# Dodekatron.net
KiCad netlist of a schematic drawn in EAGLE
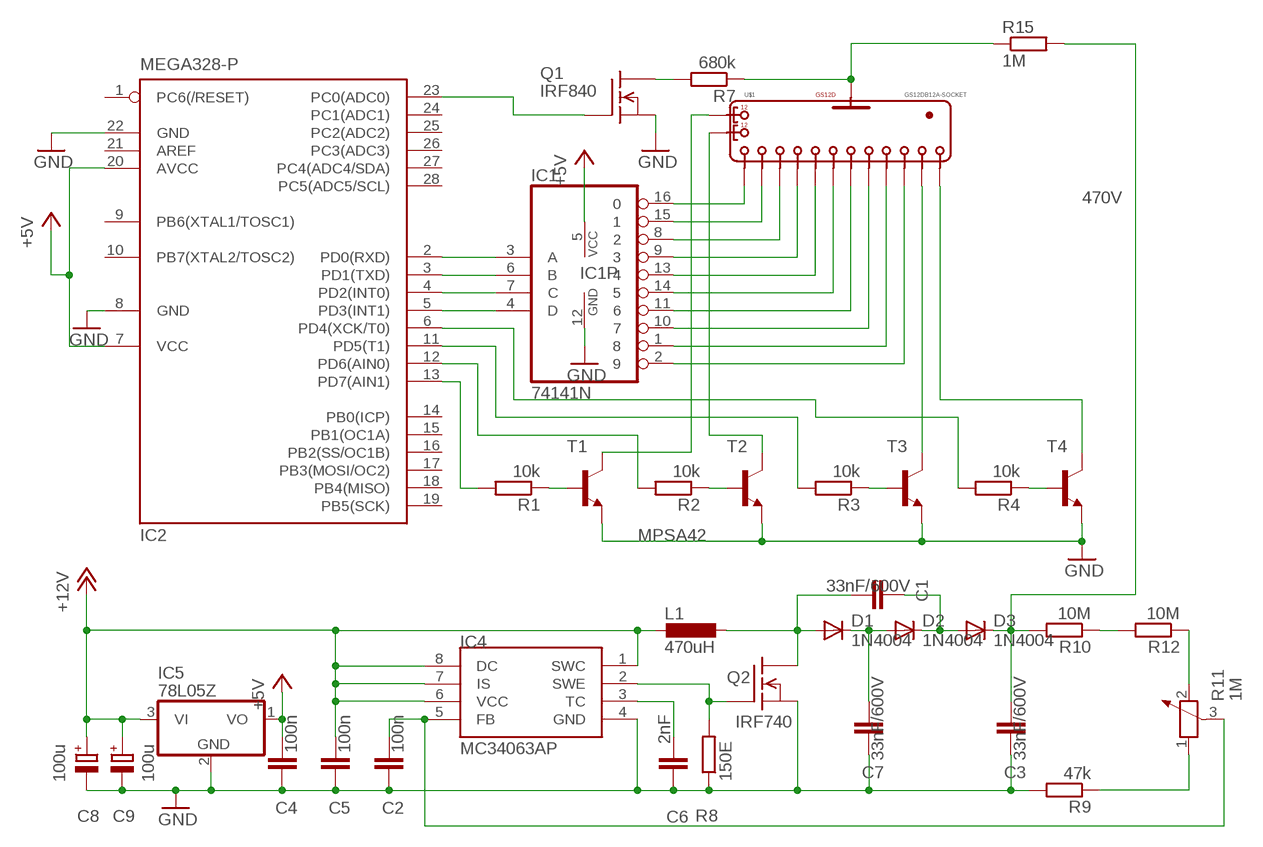
[diagram p0: schematic, sheet 1]

(export (version "E")
  (design (tool "Eeschema 10.0.6"))
  (components
    (comp (ref "C1")
      (value "33nF/600V")
      (footprint "eagle-import:C025-025X050")
      (libsource (lib "eagle-import") (part "C-EU025-025X050"))
    )
    (comp (ref "C2")
      (value "100n")
      (footprint "eagle-import:C025-025X050")
      (libsource (lib "eagle-import") (part "C-EU025-025X050"))
    )
    (comp (ref "C3")
      (value "33nF/600V")
      (footprint "eagle-import:C025-025X050")
      (libsource (lib "eagle-import") (part "C-EU025-025X050"))
    )
    (comp (ref "C4")
      (value "100n")
      (footprint "eagle-import:C025-025X050")
      (libsource (lib "eagle-import") (part "C-EU025-025X050"))
    )
    (comp (ref "C5")
      (value "100n")
      (footprint "eagle-import:C025-025X050")
      (libsource (lib "eagle-import") (part "C-EU025-025X050"))
    )
    (comp (ref "C6")
      (value "2nF")
      (footprint "eagle-import:C025-025X050")
      (libsource (lib "eagle-import") (part "C-EU025-025X050"))
    )
    (comp (ref "C7")
      (value "33nF/600V")
      (footprint "eagle-import:C025-025X050")
      (libsource (lib "eagle-import") (part "C-EU025-025X050"))
    )
    (comp (ref "C8")
      (value "100u")
      (footprint "eagle-import:TAP5-80")
      (libsource (lib "eagle-import") (part "CPOL-EUTAP5-80"))
    )
    (comp (ref "C9")
      (value "100u")
      (footprint "eagle-import:TAP5-80")
      (libsource (lib "eagle-import") (part "CPOL-EUTAP5-80"))
    )
    (comp (ref "D1")
      (value "1N4004")
      (footprint "eagle-import:DO41-10")
      (libsource (lib "eagle-import") (part "1N4004"))
    )
    (comp (ref "D2")
      (value "1N4004")
      (footprint "eagle-import:DO41-10")
      (libsource (lib "eagle-import") (part "1N4004"))
    )
    (comp (ref "D3")
      (value "1N4004")
      (footprint "eagle-import:DO41-10")
      (libsource (lib "eagle-import") (part "1N4004"))
    )
    (comp (ref "IC1")
      (value "74141N")
      (footprint "eagle-import:DIL16")
      (libsource (lib "eagle-import") (part "74141N"))
    )
    (comp (ref "IC2")
      (value "MEGA328-P")
      (footprint "eagle-import:DIL28-3")
      (libsource (lib "eagle-import") (part "MEGA8-P"))
    )
    (comp (ref "IC4")
      (value "MC34063AP")
      (footprint "eagle-import:DIL08")
      (libsource (lib "eagle-import") (part "MC34063AP"))
    )
    (comp (ref "IC5")
      (value "78L05Z")
      (footprint "eagle-import:TO92")
      (libsource (lib "eagle-import") (part "78ZL05"))
    )
    (comp (ref "L1")
      (value "470uH")
      (footprint "eagle-import:6000-XXXX-RC")
      (libsource (lib "eagle-import") (part "L-EU6000-XXX-RC"))
    )
    (comp (ref "Q1")
      (value "IRF840")
      (footprint "eagle-import:TO220")
      (libsource (lib "eagle-import") (part "IRF840"))
    )
    (comp (ref "Q2")
      (value "IRF740")
      (footprint "eagle-import:TO220")
      (libsource (lib "eagle-import") (part "IRF620"))
    )
    (comp (ref "R1")
      (value "10k")
      (footprint "eagle-import:0207_10")
      (libsource (lib "eagle-import") (part "R-EU_0207/10"))
    )
    (comp (ref "R2")
      (value "10k")
      (footprint "eagle-import:0207_10")
      (libsource (lib "eagle-import") (part "R-EU_0207/10"))
    )
    (comp (ref "R3")
      (value "10k")
      (footprint "eagle-import:0207_10")
      (libsource (lib "eagle-import") (part "R-EU_0207/10"))
    )
    (comp (ref "R4")
      (value "10k")
      (footprint "eagle-import:0207_10")
      (libsource (lib "eagle-import") (part "R-EU_0207/10"))
    )
    (comp (ref "R7")
      (value "680k")
      (footprint "eagle-import:0207_10")
      (libsource (lib "eagle-import") (part "R-EU_0207/10"))
    )
    (comp (ref "R8")
      (value "150E")
      (footprint "eagle-import:0207_10")
      (libsource (lib "eagle-import") (part "R-EU_0207/10"))
    )
    (comp (ref "R9")
      (value "47k")
      (footprint "eagle-import:0207_10")
      (libsource (lib "eagle-import") (part "R-EU_0207/10"))
    )
    (comp (ref "R10")
      (value "10M")
      (footprint "eagle-import:0207_10")
      (libsource (lib "eagle-import") (part "R-EU_0207/10"))
    )
    (comp (ref "R11")
      (value "1M")
      (footprint "eagle-import:PT-SPIN")
      (libsource (lib "eagle-import") (part "POTENTIOMETER_PT_SPIN"))
    )
    (comp (ref "R12")
      (value "10M")
      (footprint "eagle-import:0207_10")
      (libsource (lib "eagle-import") (part "R-EU_0207/10"))
    )
    (comp (ref "R15")
      (value "1M")
      (footprint "eagle-import:0207_10")
      (libsource (lib "eagle-import") (part "R-EU_0207/10"))
    )
    (comp (ref "T1")
      (value "MPSA42")
      (footprint "eagle-import:TO92-CBE")
      (libsource (lib "eagle-import") (part "-NPN-TO92-CBEMPSA42"))
    )
    (comp (ref "T2")
      (value "MPSA42-NPN-TO92-CBE")
      (footprint "eagle-import:TO92-CBE")
      (libsource (lib "eagle-import") (part "-NPN-TO92-CBEMPSA42"))
    )
    (comp (ref "T3")
      (value "MPSA42-NPN-TO92-CBE")
      (footprint "eagle-import:TO92-CBE")
      (libsource (lib "eagle-import") (part "-NPN-TO92-CBEMPSA42"))
    )
    (comp (ref "T4")
      (value "MPSA42-NPN-TO92-CBE")
      (footprint "eagle-import:TO92-CBE")
      (libsource (lib "eagle-import") (part "-NPN-TO92-CBEMPSA42"))
    )
    (comp (ref "U$1")
      (value "GS12DB12A-SOCKET")
      (footprint "eagle-import:B12A-SOCKET")
      (libsource (lib "eagle-import") (part "GS12DB12A-SOCKET"))
    )
  )
  (nets
    (net (code "1") (name "+5V") (class "Default")
      (node (ref "C4") (pin "1") (pinfunction "1_1") (pintype "passive"))
      (node (ref "IC1") (pin "5") (pinfunction "VCC_5") (pintype "power_in"))
      (node (ref "IC2") (pin "20") (pinfunction "AVCC_20") (pintype "power_in"))
      (node (ref "IC2") (pin "7") (pinfunction "VCC_7") (pintype "power_in"))
      (node (ref "IC5") (pin "1") (pinfunction "VO_1") (pintype "passive"))
    )
    (net (code "2") (name "+12V") (class "Default")
      (node (ref "C5") (pin "1") (pinfunction "1_1") (pintype "passive"))
      (node (ref "C8") (pin "+") (pinfunction "+_+") (pintype "passive"))
      (node (ref "C9") (pin "+") (pinfunction "+_+") (pintype "passive"))
      (node (ref "IC4") (pin "1") (pinfunction "SWC_1") (pintype "passive"))
      (node (ref "IC4") (pin "6") (pinfunction "VCC_6") (pintype "passive"))
      (node (ref "IC4") (pin "7") (pinfunction "IS_7") (pintype "passive"))
      (node (ref "IC4") (pin "8") (pinfunction "DC_8") (pintype "passive"))
      (node (ref "IC5") (pin "3") (pinfunction "VI_3") (pintype "input"))
      (node (ref "L1") (pin "2") (pinfunction "2_2") (pintype "passive"))
    )
    (net (code "3") (name "/470V") (class "Default")
      (node (ref "C3") (pin "1") (pinfunction "1_1") (pintype "passive"))
      (node (ref "D3") (pin "C") (pinfunction "C_C") (pintype "passive"))
      (node (ref "R10") (pin "2") (pinfunction "2_2") (pintype "passive"))
      (node (ref "R15") (pin "2") (pinfunction "2_2") (pintype "passive"))
    )
    (net (code "4") (name "GND") (class "Default")
      (node (ref "C2") (pin "2") (pinfunction "2_2") (pintype "passive"))
      (node (ref "C3") (pin "2") (pinfunction "2_2") (pintype "passive"))
      (node (ref "C4") (pin "2") (pinfunction "2_2") (pintype "passive"))
      (node (ref "C5") (pin "2") (pinfunction "2_2") (pintype "passive"))
      (node (ref "C6") (pin "2") (pinfunction "2_2") (pintype "passive"))
      (node (ref "C7") (pin "2") (pinfunction "2_2") (pintype "passive"))
      (node (ref "C8") (pin "-") (pinfunction "-_-") (pintype "passive"))
      (node (ref "C9") (pin "-") (pinfunction "-_-") (pintype "passive"))
      (node (ref "IC1") (pin "12") (pinfunction "GND_12") (pintype "power_in"))
      (node (ref "IC2") (pin "22") (pinfunction "GND_22") (pintype "power_in"))
      (node (ref "IC2") (pin "8") (pinfunction "GND_8") (pintype "power_in"))
      (node (ref "IC4") (pin "4") (pinfunction "GND_4") (pintype "passive"))
      (node (ref "IC5") (pin "2") (pinfunction "GND_2") (pintype "passive"))
      (node (ref "Q1") (pin "3") (pinfunction "S_3") (pintype "passive"))
      (node (ref "Q2") (pin "3") (pinfunction "S_3") (pintype "passive"))
      (node (ref "R8") (pin "1") (pinfunction "1_1") (pintype "passive"))
      (node (ref "R9") (pin "2") (pinfunction "2_2") (pintype "passive"))
      (node (ref "T1") (pin "E") (pinfunction "E_E") (pintype "passive"))
      (node (ref "T2") (pin "E") (pinfunction "E_E") (pintype "passive"))
      (node (ref "T3") (pin "E") (pinfunction "E_E") (pintype "passive"))
      (node (ref "T4") (pin "E") (pinfunction "E_E") (pintype "passive"))
    )
    (net (code "5") (name "Net-(C1-Pad2)") (class "Default")
      (node (ref "C1") (pin "2") (pinfunction "2_2") (pintype "passive"))
      (node (ref "D2") (pin "C") (pinfunction "C_C") (pintype "passive"))
      (node (ref "D3") (pin "A") (pinfunction "A_A") (pintype "passive"))
    )
    (net (code "6") (name "Net-(C7-Pad1)") (class "Default")
      (node (ref "C7") (pin "1") (pinfunction "1_1") (pintype "passive"))
      (node (ref "D1") (pin "C") (pinfunction "C_C") (pintype "passive"))
      (node (ref "D2") (pin "A") (pinfunction "A_A") (pintype "passive"))
    )
    (net (code "7") (name "Net-(IC1A-0)") (class "Default")
      (node (ref "IC1") (pin "16") (pinfunction "0_16") (pintype "open_collector"))
      (node (ref "U$1") (pin "P$2") (pinfunction "P$12_P$2") (pintype "bidirectional"))
    )
    (net (code "8") (name "Net-(IC1A-1)") (class "Default")
      (node (ref "IC1") (pin "15") (pinfunction "1_15") (pintype "open_collector"))
      (node (ref "U$1") (pin "P$3") (pinfunction "P$11_P$3") (pintype "bidirectional"))
    )
    (net (code "9") (name "Net-(IC1A-2)") (class "Default")
      (node (ref "IC1") (pin "8") (pinfunction "2_8") (pintype "open_collector"))
      (node (ref "U$1") (pin "P$4") (pinfunction "P$10_P$4") (pintype "bidirectional"))
    )
    (net (code "10") (name "Net-(IC1A-3)") (class "Default")
      (node (ref "IC1") (pin "9") (pinfunction "3_9") (pintype "open_collector"))
      (node (ref "U$1") (pin "P$5") (pinfunction "P$09_P$5") (pintype "bidirectional"))
    )
    (net (code "11") (name "Net-(IC1A-4)") (class "Default")
      (node (ref "IC1") (pin "13") (pinfunction "4_13") (pintype "open_collector"))
      (node (ref "U$1") (pin "P$6") (pinfunction "P$08_P$6") (pintype "bidirectional"))
    )
    (net (code "12") (name "Net-(IC1A-5)") (class "Default")
      (node (ref "IC1") (pin "14") (pinfunction "5_14") (pintype "open_collector"))
      (node (ref "U$1") (pin "P$7") (pinfunction "P$07_P$7") (pintype "bidirectional"))
    )
    (net (code "13") (name "Net-(IC1A-6)") (class "Default")
      (node (ref "IC1") (pin "11") (pinfunction "6_11") (pintype "open_collector"))
      (node (ref "U$1") (pin "P$8") (pinfunction "P$06_P$8") (pintype "bidirectional"))
    )
    (net (code "14") (name "Net-(IC1A-7)") (class "Default")
      (node (ref "IC1") (pin "10") (pinfunction "7_10") (pintype "open_collector"))
      (node (ref "U$1") (pin "P$9") (pinfunction "P$05_P$9") (pintype "bidirectional"))
    )
    (net (code "15") (name "Net-(IC1A-8)") (class "Default")
      (node (ref "IC1") (pin "1") (pinfunction "8_1") (pintype "open_collector"))
      (node (ref "U$1") (pin "P$10") (pinfunction "P$04_P$10") (pintype "bidirectional"))
    )
    (net (code "16") (name "Net-(IC1A-9)") (class "Default")
      (node (ref "IC1") (pin "2") (pinfunction "9_2") (pintype "open_collector"))
      (node (ref "U$1") (pin "P$11") (pinfunction "P$03_P$11") (pintype "bidirectional"))
    )
    (net (code "17") (name "Net-(IC1A-A)") (class "Default")
      (node (ref "IC1") (pin "3") (pinfunction "A_3") (pintype "input"))
      (node (ref "IC2") (pin "2") (pinfunction "PD0(RXD)_2") (pintype "bidirectional"))
    )
    (net (code "18") (name "Net-(IC1A-B)") (class "Default")
      (node (ref "IC1") (pin "6") (pinfunction "B_6") (pintype "input"))
      (node (ref "IC2") (pin "3") (pinfunction "PD1(TXD)_3") (pintype "bidirectional"))
    )
    (net (code "19") (name "Net-(IC1A-C)") (class "Default")
      (node (ref "IC1") (pin "7") (pinfunction "C_7") (pintype "input"))
      (node (ref "IC2") (pin "4") (pinfunction "PD2(INT0)_4") (pintype "bidirectional"))
    )
    (net (code "20") (name "Net-(IC1A-D)") (class "Default")
      (node (ref "IC1") (pin "4") (pinfunction "D_4") (pintype "input"))
      (node (ref "IC2") (pin "5") (pinfunction "PD3(INT1)_5") (pintype "bidirectional"))
    )
    (net (code "21") (name "Net-(IC2-PC0(ADC0))") (class "Default")
      (node (ref "IC2") (pin "23") (pinfunction "PC0(ADC0)_23") (pintype "bidirectional"))
      (node (ref "Q1") (pin "1") (pinfunction "G_1") (pintype "passive"))
    )
    (net (code "22") (name "Net-(IC2-PD4(XCK{slash}T0))") (class "Default")
      (node (ref "IC2") (pin "6") (pinfunction "PD4(XCK/T0)_6") (pintype "bidirectional"))
      (node (ref "R4") (pin "2") (pinfunction "2_2") (pintype "passive"))
    )
    (net (code "23") (name "Net-(IC2-PD5(T1))") (class "Default")
      (node (ref "IC2") (pin "11") (pinfunction "PD5(T1)_11") (pintype "bidirectional"))
      (node (ref "R3") (pin "2") (pinfunction "2_2") (pintype "passive"))
    )
    (net (code "24") (name "Net-(IC2-PD6(AIN0))") (class "Default")
      (node (ref "IC2") (pin "12") (pinfunction "PD6(AIN0)_12") (pintype "bidirectional"))
      (node (ref "R2") (pin "2") (pinfunction "2_2") (pintype "passive"))
    )
    (net (code "25") (name "Net-(IC2-PD7(AIN1))") (class "Default")
      (node (ref "IC2") (pin "13") (pinfunction "PD7(AIN1)_13") (pintype "bidirectional"))
      (node (ref "R1") (pin "2") (pinfunction "2_2") (pintype "passive"))
    )
    (net (code "26") (name "Net-(IC4-FB)") (class "Default")
      (node (ref "C2") (pin "1") (pinfunction "1_1") (pintype "passive"))
      (node (ref "IC4") (pin "5") (pinfunction "FB_5") (pintype "passive"))
      (node (ref "R11") (pin "3") (pinfunction "3_3") (pintype "passive"))
    )
    (net (code "27") (name "Net-(IC4-SWE)") (class "Default")
      (node (ref "IC4") (pin "2") (pinfunction "SWE_2") (pintype "passive"))
      (node (ref "Q2") (pin "1") (pinfunction "G_1") (pintype "passive"))
      (node (ref "R8") (pin "2") (pinfunction "2_2") (pintype "passive"))
    )
    (net (code "28") (name "Net-(IC4-TC)") (class "Default")
      (node (ref "C6") (pin "1") (pinfunction "1_1") (pintype "passive"))
      (node (ref "IC4") (pin "3") (pinfunction "TC_3") (pintype "passive"))
    )
    (net (code "29") (name "Net-(Q1-D)") (class "Default")
      (node (ref "Q1") (pin "2") (pinfunction "D_2") (pintype "passive"))
      (node (ref "R7") (pin "2") (pinfunction "2_2") (pintype "passive"))
    )
    (net (code "30") (name "Net-(Q2-D)") (class "Default")
      (node (ref "C1") (pin "1") (pinfunction "1_1") (pintype "passive"))
      (node (ref "D1") (pin "A") (pinfunction "A_A") (pintype "passive"))
      (node (ref "L1") (pin "1") (pinfunction "1_1") (pintype "passive"))
      (node (ref "Q2") (pin "2") (pinfunction "D_2") (pintype "passive"))
    )
    (net (code "31") (name "Net-(R1-Pad1)") (class "Default")
      (node (ref "R1") (pin "1") (pinfunction "1_1") (pintype "passive"))
      (node (ref "T1") (pin "B") (pinfunction "B_B") (pintype "passive"))
    )
    (net (code "32") (name "Net-(R2-Pad1)") (class "Default")
      (node (ref "R2") (pin "1") (pinfunction "1_1") (pintype "passive"))
      (node (ref "T2") (pin "B") (pinfunction "B_B") (pintype "passive"))
    )
    (net (code "33") (name "Net-(R3-Pad1)") (class "Default")
      (node (ref "R3") (pin "1") (pinfunction "1_1") (pintype "passive"))
      (node (ref "T3") (pin "B") (pinfunction "B_B") (pintype "passive"))
    )
    (net (code "34") (name "Net-(R4-Pad1)") (class "Default")
      (node (ref "R4") (pin "1") (pinfunction "1_1") (pintype "passive"))
      (node (ref "T4") (pin "B") (pinfunction "B_B") (pintype "passive"))
    )
    (net (code "35") (name "Net-(R10-Pad1)") (class "Default")
      (node (ref "R10") (pin "1") (pinfunction "1_1") (pintype "passive"))
      (node (ref "R12") (pin "2") (pinfunction "2_2") (pintype "passive"))
    )
    (net (code "36") (name "Net-(R11-Pad1)") (class "Default")
      (node (ref "R11") (pin "1") (pinfunction "1_1") (pintype "passive"))
      (node (ref "R9") (pin "1") (pinfunction "1_1") (pintype "passive"))
    )
    (net (code "37") (name "Net-(R11-Pad2)") (class "Default")
      (node (ref "R11") (pin "2") (pinfunction "2_2") (pintype "passive"))
      (node (ref "R12") (pin "1") (pinfunction "1_1") (pintype "passive"))
    )
    (net (code "38") (name "Net-(U$1-P$01)") (class "Default")
      (node (ref "T4") (pin "C") (pinfunction "C_C") (pintype "passive"))
      (node (ref "U$1") (pin "P$1") (pinfunction "P$01_P$1") (pintype "bidirectional"))
    )
    (net (code "39") (name "Net-(U$1-P$02)") (class "Default")
      (node (ref "T3") (pin "C") (pinfunction "C_C") (pintype "passive"))
      (node (ref "U$1") (pin "P$12") (pinfunction "P$02_P$12") (pintype "bidirectional"))
    )
    (net (code "40") (name "Net-(U$1-P$A)") (class "Default")
      (node (ref "R15") (pin "1") (pinfunction "1_1") (pintype "passive"))
      (node (ref "R7") (pin "1") (pinfunction "1_1") (pintype "passive"))
      (node (ref "U$1") (pin "P$0") (pinfunction "P$A_P$0") (pintype "bidirectional"))
    )
    (net (code "41") (name "Net-(U$1-P$G1)") (class "Default")
      (node (ref "T1") (pin "C") (pinfunction "C_C") (pintype "passive"))
      (node (ref "U$1") (pin "P$YEL") (pinfunction "P$G1_P$YEL") (pintype "bidirectional"))
    )
    (net (code "42") (name "Net-(U$1-P$G2)") (class "Default")
      (node (ref "T2") (pin "C") (pinfunction "C_C") (pintype "passive"))
      (node (ref "U$1") (pin "P$GRN") (pinfunction "P$G2_P$GRN") (pintype "bidirectional"))
    )
    (net (code "43") (name "unconnected-(IC2-AREF-Pad21)") (class "Default")
      (node (ref "IC2") (pin "21") (pinfunction "AREF_21") (pintype "passive"))
    )
    (net (code "44") (name "unconnected-(IC2-PB0(ICP)-Pad14)") (class "Default")
      (node (ref "IC2") (pin "14") (pinfunction "PB0(ICP)_14") (pintype "bidirectional"))
    )
    (net (code "45") (name "unconnected-(IC2-PB1(OC1A)-Pad15)") (class "Default")
      (node (ref "IC2") (pin "15") (pinfunction "PB1(OC1A)_15") (pintype "bidirectional"))
    )
    (net (code "46") (name "unconnected-(IC2-PB2(SS{slash}OC1B)-Pad16)") (class "Default")
      (node (ref "IC2") (pin "16") (pinfunction "PB2(SS/OC1B)_16") (pintype "bidirectional"))
    )
    (net (code "47") (name "unconnected-(IC2-PB3(MOSI{slash}OC2)-Pad17)") (class "Default")
      (node (ref "IC2") (pin "17") (pinfunction "PB3(MOSI/OC2)_17") (pintype "bidirectional"))
    )
    (net (code "48") (name "unconnected-(IC2-PB4(MISO)-Pad18)") (class "Default")
      (node (ref "IC2") (pin "18") (pinfunction "PB4(MISO)_18") (pintype "bidirectional"))
    )
    (net (code "49") (name "unconnected-(IC2-PB5(SCK)-Pad19)") (class "Default")
      (node (ref "IC2") (pin "19") (pinfunction "PB5(SCK)_19") (pintype "bidirectional"))
    )
    (net (code "50") (name "unconnected-(IC2-PB6(XTAL1{slash}TOSC1)-Pad9)") (class "Default")
      (node (ref "IC2") (pin "9") (pinfunction "PB6(XTAL1/TOSC1)_9") (pintype "bidirectional"))
    )
    (net (code "51") (name "unconnected-(IC2-PB7(XTAL2{slash}TOSC2)-Pad10)") (class "Default")
      (node (ref "IC2") (pin "10") (pinfunction "PB7(XTAL2/TOSC2)_10") (pintype "bidirectional"))
    )
    (net (code "52") (name "unconnected-(IC2-PC1(ADC1)-Pad24)") (class "Default")
      (node (ref "IC2") (pin "24") (pinfunction "PC1(ADC1)_24") (pintype "bidirectional"))
    )
    (net (code "53") (name "unconnected-(IC2-PC2(ADC2)-Pad25)") (class "Default")
      (node (ref "IC2") (pin "25") (pinfunction "PC2(ADC2)_25") (pintype "bidirectional"))
    )
    (net (code "54") (name "unconnected-(IC2-PC3(ADC3)-Pad26)") (class "Default")
      (node (ref "IC2") (pin "26") (pinfunction "PC3(ADC3)_26") (pintype "bidirectional"))
    )
    (net (code "55") (name "unconnected-(IC2-PC4(ADC4{slash}SDA)-Pad27)") (class "Default")
      (node (ref "IC2") (pin "27") (pinfunction "PC4(ADC4/SDA)_27") (pintype "bidirectional"))
    )
    (net (code "56") (name "unconnected-(IC2-PC5(ADC5{slash}SCL)-Pad28)") (class "Default")
      (node (ref "IC2") (pin "28") (pinfunction "PC5(ADC5/SCL)_28") (pintype "bidirectional"))
    )
    (net (code "57") (name "unconnected-(IC2-PC6({slash}RESET)-Pad1)") (class "Default")
      (node (ref "IC2") (pin "1") (pinfunction "PC6(/RESET)_1") (pintype "bidirectional"))
    )
  )
)
